# WallPower_5V2A.net
KiCad netlist of a schematic drawn in EAGLE
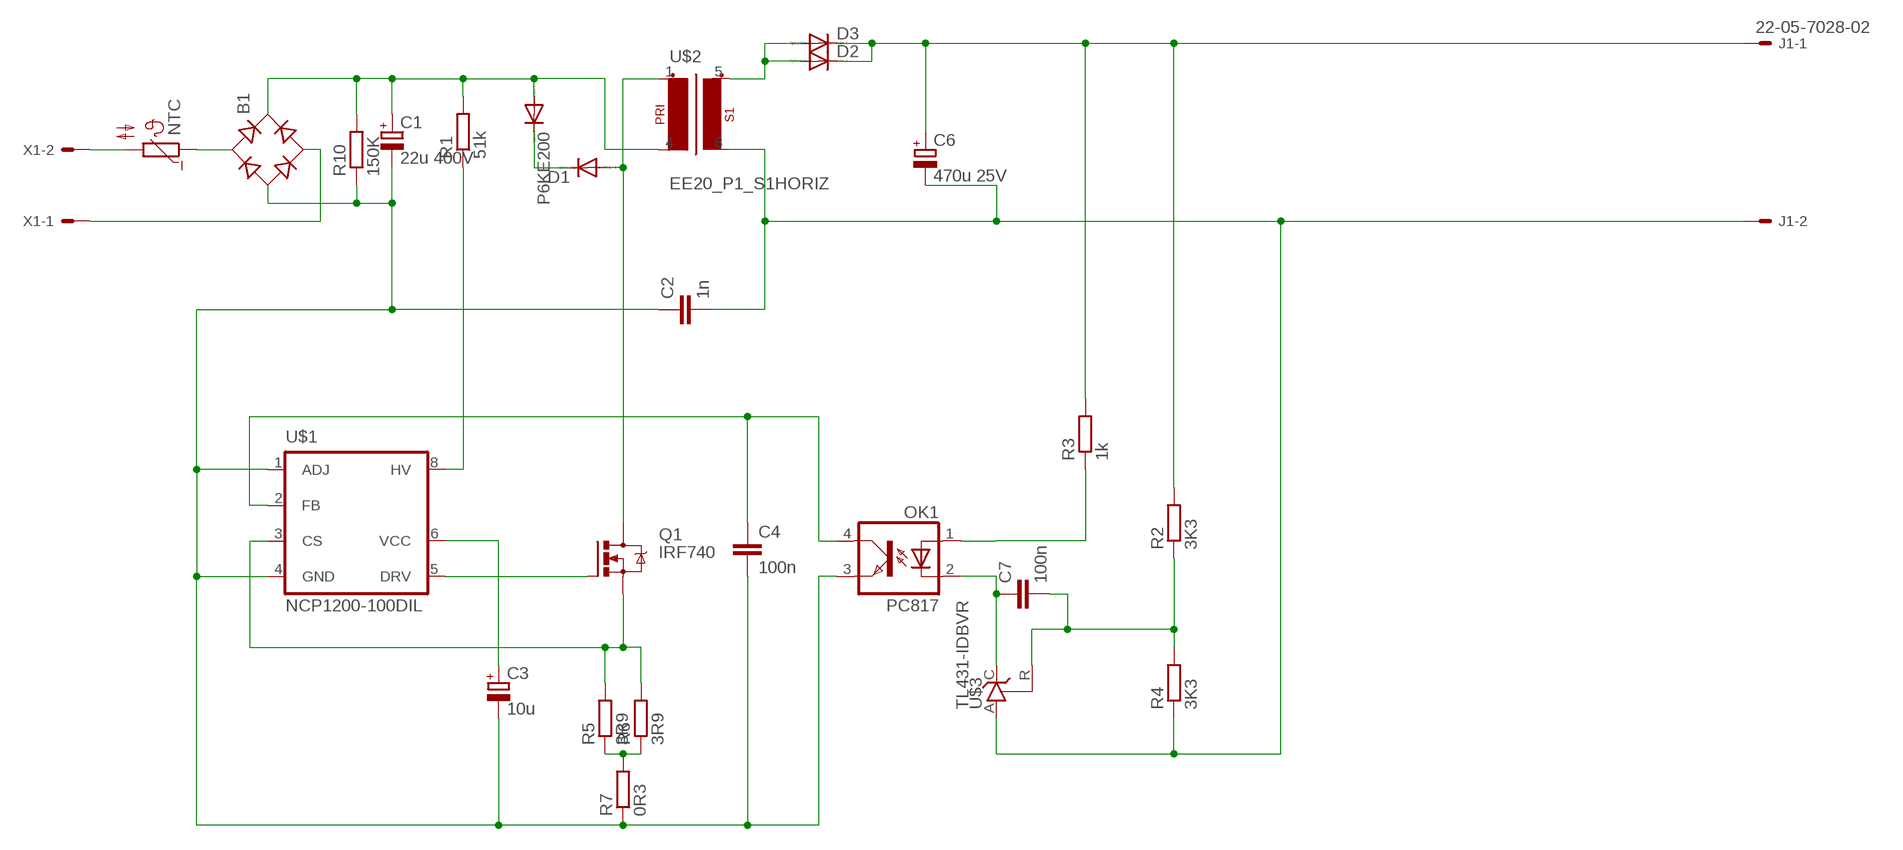
[diagram p0: schematic, sheet 1]

(export (version "E")
  (design (tool "Eeschema 10.0.6"))
  (components
    (comp (ref "B1")
      (value "RB1A")
      (footprint "eagle-import:RB1A")
      (libsource (lib "eagle-import") (part "RB1A"))
    )
    (comp (ref "C1")
      (value "22u 400V")
      (footprint "eagle-import:E5-13")
      (libsource (lib "eagle-import") (part "CPOL-EUE5-13"))
    )
    (comp (ref "C2")
      (value "1n")
      (footprint "eagle-import:C050-024X044")
      (libsource (lib "eagle-import") (part "C-EU050-024X044"))
    )
    (comp (ref "C3")
      (value "10u")
      (footprint "eagle-import:E2,5-5")
      (libsource (lib "eagle-import") (part "CPOL-EUE2.5-5"))
    )
    (comp (ref "C4")
      (value "100n")
      (footprint "eagle-import:C0805")
      (libsource (lib "eagle-import") (part "C-EUC0805"))
    )
    (comp (ref "C6")
      (value "470u 25V")
      (footprint "eagle-import:E2,5-7")
      (libsource (lib "eagle-import") (part "CPOL-EUE2.5-7"))
    )
    (comp (ref "C7")
      (value "100n")
      (footprint "eagle-import:C0805")
      (libsource (lib "eagle-import") (part "C-EUC0805"))
    )
    (comp (ref "D1")
      (value "DIODE-DO-214AC")
      (footprint "eagle-import:DO-214AC")
      (libsource (lib "eagle-import") (part "DIODE-DO-214AC"))
    )
    (comp (ref "D2")
      (value "DIODE-DO-214AC")
      (footprint "eagle-import:DO-214AC")
      (libsource (lib "eagle-import") (part "DIODE-DO-214AC"))
    )
    (comp (ref "D3")
      (value "DIODE-DO-214AC")
      (footprint "eagle-import:DO-214AC")
      (libsource (lib "eagle-import") (part "DIODE-DO-214AC"))
    )
    (comp (ref "J1")
      (value "22-05-7028-02")
      (footprint "eagle-import:7395-02")
      (libsource (lib "eagle-import") (part "22-?-0205-7028"))
    )
    (comp (ref "NTC")
      (value "B57164")
      (footprint "eagle-import:B57164")
      (fields (field (name "MPN") "B57164K474K52"))
      (libsource (lib "eagle-import") (part "B57164"))
    )
    (comp (ref "OK1")
      (value "PC817")
      (footprint "eagle-import:DIL04")
      (fields (field (name "MPN") "PC817X4J000F"))
      (libsource (lib "eagle-import") (part "PC817"))
    )
    (comp (ref "P6KE200")
      (value "DIODE-DO15-12")
      (footprint "eagle-import:DO15-12")
      (libsource (lib "eagle-import") (part "DIODE-DO15-12"))
    )
    (comp (ref "Q1")
      (value "IRF740")
      (footprint "eagle-import:TO220BV")
      (libsource (lib "eagle-import") (part "IRF740"))
    )
    (comp (ref "R1")
      (value "51k")
      (footprint "eagle-import:0922_22")
      (libsource (lib "eagle-import") (part "R-EU_0922/22"))
    )
    (comp (ref "R2")
      (value "3K3")
      (footprint "eagle-import:R1206")
      (libsource (lib "eagle-import") (part "R-EU_R1206"))
    )
    (comp (ref "R3")
      (value "1k")
      (footprint "eagle-import:R1206")
      (libsource (lib "eagle-import") (part "R-EU_R1206"))
    )
    (comp (ref "R4")
      (value "3K3")
      (footprint "eagle-import:R1206")
      (libsource (lib "eagle-import") (part "R-EU_R1206"))
    )
    (comp (ref "R5")
      (value "3R9")
      (footprint "eagle-import:0411_12")
      (libsource (lib "eagle-import") (part "R-EU_0411/12"))
    )
    (comp (ref "R6")
      (value "3R9")
      (footprint "eagle-import:0411_12")
      (libsource (lib "eagle-import") (part "R-EU_0411/12"))
    )
    (comp (ref "R7")
      (value "0R3")
      (footprint "eagle-import:0411_12")
      (libsource (lib "eagle-import") (part "R-EU_0411/12"))
    )
    (comp (ref "R10")
      (value "150K")
      (footprint "eagle-import:0204_7")
      (libsource (lib "eagle-import") (part "R-EU_0204/7"))
    )
    (comp (ref "U$1")
      (value "NCP1200-100DIL")
      (footprint "eagle-import:DIP08")
      (libsource (lib "eagle-import") (part "NCP1200-100DIL"))
    )
    (comp (ref "U$2")
      (value "EE20_P1_S1HORIZ")
      (footprint "eagle-import:EE20_P1_S1_HORIZ_REV")
      (libsource (lib "eagle-import") (part "EE20_P1_S1HORIZ"))
    )
    (comp (ref "U$3")
      (value "TL431-IDBVR")
      (footprint "eagle-import:SOT23-5")
      (libsource (lib "eagle-import") (part "TL431-IDBVR"))
    )
    (comp (ref "X1")
      (value "KK-156-2")
      (footprint "eagle-import:KK-156-2")
      (libsource (lib "eagle-import") (part "KK-156-2"))
    )
  )
  (nets
    (net (code "1") (name "Net-(B1-PadAC1)") (class "Default")
      (node (ref "B1") (pin "AC1") (pinfunction "AC1_AC1") (pintype "passive"))
      (node (ref "NTC") (pin "1") (pinfunction "1_1") (pintype "passive"))
    )
    (net (code "2") (name "Net-(C7-Pad2)") (class "Default")
      (node (ref "C7") (pin "2") (pinfunction "2_2") (pintype "passive"))
      (node (ref "R2") (pin "1") (pinfunction "1_1") (pintype "passive"))
      (node (ref "R4") (pin "2") (pinfunction "2_2") (pintype "passive"))
      (node (ref "U$3") (pin "R") (pinfunction "R_R") (pintype "passive"))
    )
    (net (code "3") (name "Net-(D1-PadC)") (class "Default")
      (node (ref "D1") (pin "C") (pinfunction "C_C") (pintype "passive"))
      (node (ref "P6KE200") (pin "C") (pinfunction "C_C") (pintype "passive"))
    )
    (net (code "4") (name "Net-(J1A-S)") (class "Default")
      (node (ref "C6") (pin "+") (pinfunction "+_+") (pintype "passive"))
      (node (ref "D2") (pin "C") (pinfunction "C_C") (pintype "passive"))
      (node (ref "D3") (pin "C") (pinfunction "C_C") (pintype "passive"))
      (node (ref "J1") (pin "1") (pinfunction "S_1") (pintype "passive"))
      (node (ref "R2") (pin "2") (pinfunction "2_2") (pintype "passive"))
      (node (ref "R3") (pin "2") (pinfunction "2_2") (pintype "passive"))
    )
    (net (code "5") (name "Net-(J1B-S)") (class "Default")
      (node (ref "C2") (pin "2") (pinfunction "2_2") (pintype "passive"))
      (node (ref "C6") (pin "-") (pinfunction "-_-") (pintype "passive"))
      (node (ref "J1") (pin "2") (pinfunction "S_2") (pintype "passive"))
      (node (ref "R4") (pin "1") (pinfunction "1_1") (pintype "passive"))
      (node (ref "U$2") (pin "8") (pinfunction "S1-2_8") (pintype "passive"))
      (node (ref "U$3") (pin "A") (pinfunction "A_A") (pintype "passive"))
    )
    (net (code "6") (name "Net-(OK1-A)") (class "Default")
      (node (ref "OK1") (pin "1") (pinfunction "A_1") (pintype "passive"))
      (node (ref "R3") (pin "1") (pinfunction "1_1") (pintype "passive"))
    )
    (net (code "7") (name "Net-(OK1-C)") (class "Default")
      (node (ref "C7") (pin "1") (pinfunction "1_1") (pintype "passive"))
      (node (ref "OK1") (pin "2") (pinfunction "C_2") (pintype "passive"))
      (node (ref "U$3") (pin "C") (pinfunction "C_C") (pintype "passive"))
    )
    (net (code "8") (name "Net-(OK1-COL)") (class "Default")
      (node (ref "C4") (pin "1") (pinfunction "1_1") (pintype "passive"))
      (node (ref "OK1") (pin "4") (pinfunction "COL_4") (pintype "passive"))
      (node (ref "U$1") (pin "2") (pinfunction "FB_2") (pintype "input"))
    )
    (net (code "9") (name "Net-(OK1-EMIT)") (class "Default")
      (node (ref "B1") (pin "-") (pinfunction "-_-") (pintype "passive"))
      (node (ref "C1") (pin "-") (pinfunction "-_-") (pintype "passive"))
      (node (ref "C2") (pin "1") (pinfunction "1_1") (pintype "passive"))
      (node (ref "C3") (pin "-") (pinfunction "-_-") (pintype "passive"))
      (node (ref "C4") (pin "2") (pinfunction "2_2") (pintype "passive"))
      (node (ref "OK1") (pin "3") (pinfunction "EMIT_3") (pintype "passive"))
      (node (ref "R10") (pin "1") (pinfunction "1_1") (pintype "passive"))
      (node (ref "R7") (pin "1") (pinfunction "1_1") (pintype "passive"))
      (node (ref "U$1") (pin "1") (pinfunction "ADJ_1") (pintype "passive"))
      (node (ref "U$1") (pin "4") (pinfunction "GND_4") (pintype "passive"))
    )
    (net (code "10") (name "Net-(R5-Pad1)") (class "Default")
      (node (ref "R5") (pin "1") (pinfunction "1_1") (pintype "passive"))
      (node (ref "R6") (pin "1") (pinfunction "1_1") (pintype "passive"))
      (node (ref "R7") (pin "2") (pinfunction "2_2") (pintype "passive"))
    )
    (net (code "11") (name "Net-(U$1-CS)") (class "Default")
      (node (ref "Q1") (pin "S") (pinfunction "S_S") (pintype "passive"))
      (node (ref "R5") (pin "2") (pinfunction "2_2") (pintype "passive"))
      (node (ref "R6") (pin "2") (pinfunction "2_2") (pintype "passive"))
      (node (ref "U$1") (pin "3") (pinfunction "CS_3") (pintype "input"))
    )
    (net (code "12") (name "Net-(U$1-DRV)") (class "Default")
      (node (ref "Q1") (pin "G") (pinfunction "G_G") (pintype "passive"))
      (node (ref "U$1") (pin "5") (pinfunction "DRV_5") (pintype "power_in"))
    )
    (net (code "13") (name "Net-(U$1-HV)") (class "Default")
      (node (ref "R1") (pin "1") (pinfunction "1_1") (pintype "passive"))
      (node (ref "U$1") (pin "8") (pinfunction "HV_8") (pintype "passive"))
    )
    (net (code "14") (name "Net-(U$1-VCC)") (class "Default")
      (node (ref "C3") (pin "+") (pinfunction "+_+") (pintype "passive"))
      (node (ref "U$1") (pin "6") (pinfunction "VCC_6") (pintype "output"))
    )
    (net (code "15") (name "Net-(U$2-P1-1)") (class "Default")
      (node (ref "D1") (pin "A") (pinfunction "A_A") (pintype "passive"))
      (node (ref "Q1") (pin "D") (pinfunction "D_D") (pintype "passive"))
      (node (ref "U$2") (pin "1") (pinfunction "P1-1_1") (pintype "passive"))
    )
    (net (code "16") (name "Net-(U$2-P1-2)") (class "Default")
      (node (ref "B1") (pin "+") (pinfunction "+_+") (pintype "passive"))
      (node (ref "C1") (pin "+") (pinfunction "+_+") (pintype "passive"))
      (node (ref "P6KE200") (pin "A") (pinfunction "A_A") (pintype "passive"))
      (node (ref "R1") (pin "2") (pinfunction "2_2") (pintype "passive"))
      (node (ref "R10") (pin "2") (pinfunction "2_2") (pintype "passive"))
      (node (ref "U$2") (pin "4") (pinfunction "P1-2_4") (pintype "passive"))
    )
    (net (code "17") (name "Net-(U$2-S1-1)") (class "Default")
      (node (ref "D2") (pin "A") (pinfunction "A_A") (pintype "passive"))
      (node (ref "D3") (pin "A") (pinfunction "A_A") (pintype "passive"))
      (node (ref "U$2") (pin "5") (pinfunction "S1-1_5") (pintype "passive"))
    )
    (net (code "18") (name "Net-(X1A-S)") (class "Default")
      (node (ref "B1") (pin "AC2") (pinfunction "AC2_AC2") (pintype "passive"))
      (node (ref "X1") (pin "1") (pinfunction "S_1") (pintype "passive"))
    )
    (net (code "19") (name "Net-(X1B-S)") (class "Default")
      (node (ref "NTC") (pin "2") (pinfunction "2_2") (pintype "passive"))
      (node (ref "X1") (pin "2") (pinfunction "S_2") (pintype "passive"))
    )
  )
)
